# attenuverter1.net
KiCad netlist of a schematic drawn in EAGLE
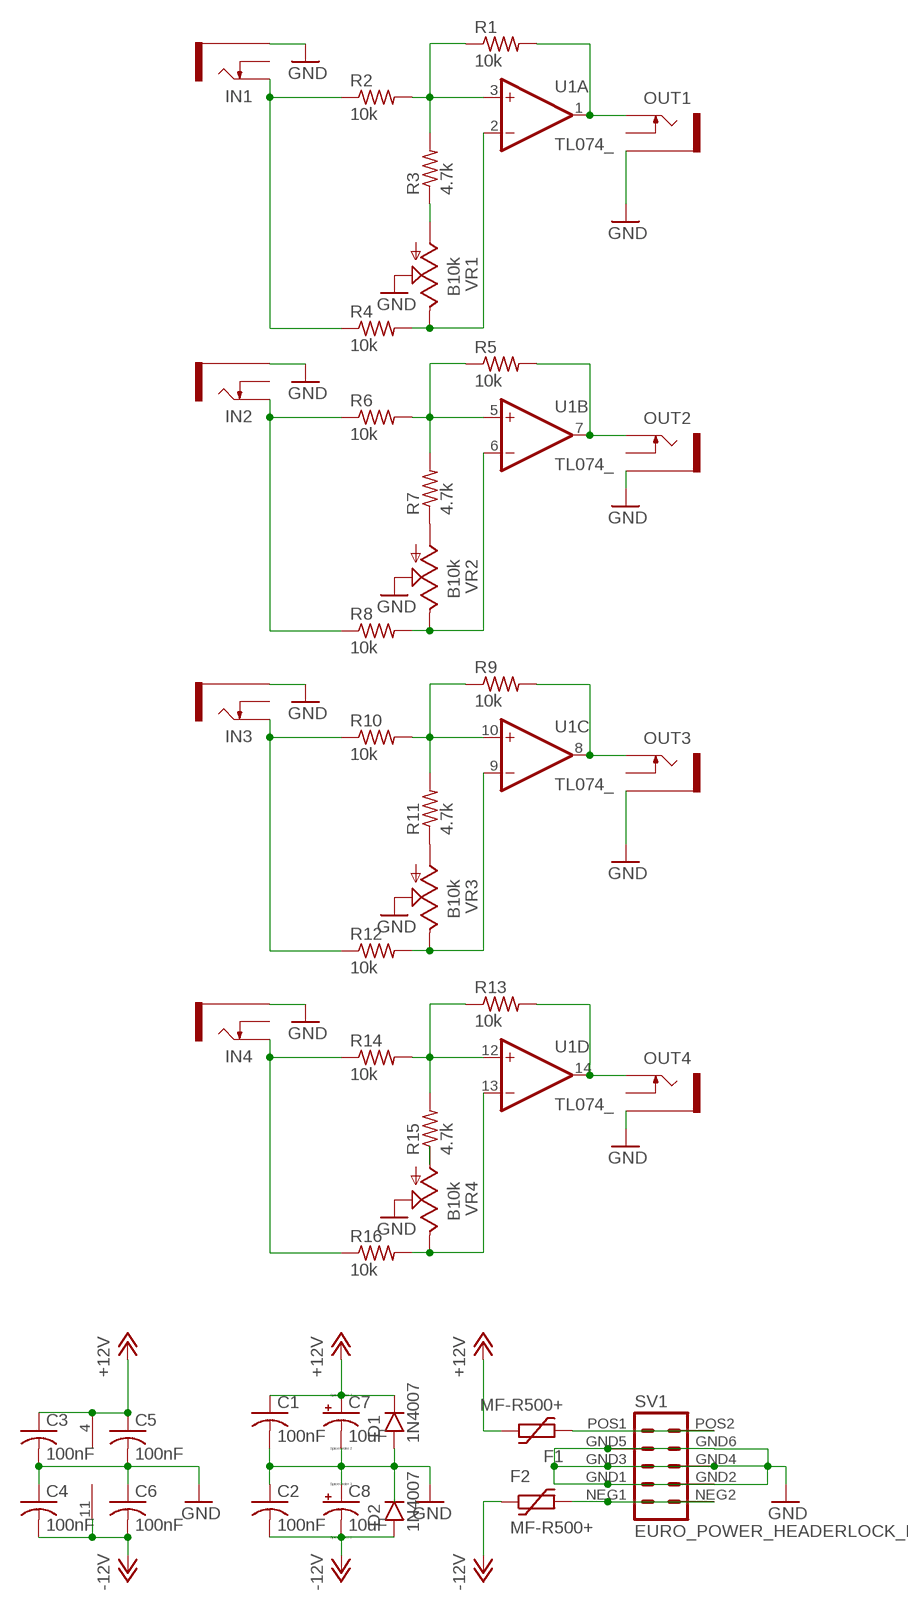
[diagram p0: schematic, sheet 1]

(export (version "E")
  (design (tool "Eeschema 10.0.6"))
  (components
    (comp (ref "C1")
      (value "100nF")
      (footprint "eagle-import:C050-055X075")
      (libsource (lib "eagle-import") (part "C-US050-055X075"))
    )
    (comp (ref "C2")
      (value "100nF")
      (footprint "eagle-import:C050-055X075")
      (libsource (lib "eagle-import") (part "C-US050-055X075"))
    )
    (comp (ref "C3")
      (value "100nF")
      (footprint "eagle-import:C050-055X075")
      (libsource (lib "eagle-import") (part "C-US050-055X075"))
    )
    (comp (ref "C4")
      (value "100nF")
      (footprint "eagle-import:C050-055X075")
      (libsource (lib "eagle-import") (part "C-US050-055X075"))
    )
    (comp (ref "C5")
      (value "100nF")
      (footprint "eagle-import:C050-055X075")
      (libsource (lib "eagle-import") (part "C-US050-055X075"))
    )
    (comp (ref "C6")
      (value "100nF")
      (footprint "eagle-import:C050-055X075")
      (libsource (lib "eagle-import") (part "C-US050-055X075"))
    )
    (comp (ref "C7")
      (value "10uF")
      (footprint "eagle-import:E2,5-6")
      (libsource (lib "eagle-import") (part "CPOL-USE2.5-6"))
    )
    (comp (ref "C8")
      (value "10uF")
      (footprint "eagle-import:E2,5-6")
      (libsource (lib "eagle-import") (part "CPOL-USE2.5-6"))
    )
    (comp (ref "D1")
      (value "1N4007")
      (footprint "eagle-import:DO41-4")
      (libsource (lib "eagle-import") (part "1N400X.4"))
    )
    (comp (ref "D2")
      (value "1N4007")
      (footprint "eagle-import:DO41-4")
      (libsource (lib "eagle-import") (part "1N400X.4"))
    )
    (comp (ref "F1")
      (value "MF-R500+")
      (footprint "eagle-import:BOURNS-MF-R")
      (libsource (lib "eagle-import") (part "MF-R500+"))
    )
    (comp (ref "F2")
      (value "MF-R500+")
      (footprint "eagle-import:BOURNS-MF-R")
      (libsource (lib "eagle-import") (part "MF-R500+"))
    )
    (comp (ref "IN1")
      (value "THONKICONNNEW")
      (footprint "eagle-import:WQP-PJ301M-12_JACK")
      (libsource (lib "eagle-import") (part "THONKICONNNEW"))
    )
    (comp (ref "IN2")
      (value "THONKICONNNEW")
      (footprint "eagle-import:WQP-PJ301M-12_JACK")
      (libsource (lib "eagle-import") (part "THONKICONNNEW"))
    )
    (comp (ref "IN3")
      (value "THONKICONNNEW")
      (footprint "eagle-import:WQP-PJ301M-12_JACK")
      (libsource (lib "eagle-import") (part "THONKICONNNEW"))
    )
    (comp (ref "IN4")
      (value "THONKICONNNEW")
      (footprint "eagle-import:WQP-PJ301M-12_JACK")
      (libsource (lib "eagle-import") (part "THONKICONNNEW"))
    )
    (comp (ref "OUT1")
      (value "THONKICONNNEW")
      (footprint "eagle-import:WQP-PJ301M-12_JACK")
      (libsource (lib "eagle-import") (part "THONKICONNNEW"))
    )
    (comp (ref "OUT2")
      (value "THONKICONNNEW")
      (footprint "eagle-import:WQP-PJ301M-12_JACK")
      (libsource (lib "eagle-import") (part "THONKICONNNEW"))
    )
    (comp (ref "OUT3")
      (value "THONKICONNNEW")
      (footprint "eagle-import:WQP-PJ301M-12_JACK")
      (libsource (lib "eagle-import") (part "THONKICONNNEW"))
    )
    (comp (ref "OUT4")
      (value "THONKICONNNEW")
      (footprint "eagle-import:WQP-PJ301M-12_JACK")
      (libsource (lib "eagle-import") (part "THONKICONNNEW"))
    )
    (comp (ref "R1")
      (value "10k")
      (footprint "eagle-import:0207_7")
      (libsource (lib "eagle-import") (part "R-US_0207/7"))
    )
    (comp (ref "R2")
      (value "10k")
      (footprint "eagle-import:0207_7")
      (libsource (lib "eagle-import") (part "R-US_0207/7"))
    )
    (comp (ref "R3")
      (value "4.7k")
      (footprint "eagle-import:0207_7")
      (libsource (lib "eagle-import") (part "R-US_0207/7"))
    )
    (comp (ref "R4")
      (value "10k")
      (footprint "eagle-import:0207_7")
      (libsource (lib "eagle-import") (part "R-US_0207/7"))
    )
    (comp (ref "R5")
      (value "10k")
      (footprint "eagle-import:0207_7")
      (libsource (lib "eagle-import") (part "R-US_0207/7"))
    )
    (comp (ref "R6")
      (value "10k")
      (footprint "eagle-import:0207_7")
      (libsource (lib "eagle-import") (part "R-US_0207/7"))
    )
    (comp (ref "R7")
      (value "4.7k")
      (footprint "eagle-import:0207_7")
      (libsource (lib "eagle-import") (part "R-US_0207/7"))
    )
    (comp (ref "R8")
      (value "10k")
      (footprint "eagle-import:0207_7")
      (libsource (lib "eagle-import") (part "R-US_0207/7"))
    )
    (comp (ref "R9")
      (value "10k")
      (footprint "eagle-import:0207_7")
      (libsource (lib "eagle-import") (part "R-US_0207/7"))
    )
    (comp (ref "R10")
      (value "10k")
      (footprint "eagle-import:0207_7")
      (libsource (lib "eagle-import") (part "R-US_0207/7"))
    )
    (comp (ref "R11")
      (value "4.7k")
      (footprint "eagle-import:0207_7")
      (libsource (lib "eagle-import") (part "R-US_0207/7"))
    )
    (comp (ref "R12")
      (value "10k")
      (footprint "eagle-import:0207_7")
      (libsource (lib "eagle-import") (part "R-US_0207/7"))
    )
    (comp (ref "R13")
      (value "10k")
      (footprint "eagle-import:0207_7")
      (libsource (lib "eagle-import") (part "R-US_0207/7"))
    )
    (comp (ref "R14")
      (value "10k")
      (footprint "eagle-import:0207_7")
      (libsource (lib "eagle-import") (part "R-US_0207/7"))
    )
    (comp (ref "R15")
      (value "4.7k")
      (footprint "eagle-import:0207_7")
      (libsource (lib "eagle-import") (part "R-US_0207/7"))
    )
    (comp (ref "R16")
      (value "10k")
      (footprint "eagle-import:0207_7")
      (libsource (lib "eagle-import") (part "R-US_0207/7"))
    )
    (comp (ref "SV1")
      (value "EURO_POWER_HEADERLOCK_PADS")
      (footprint "eagle-import:EURO_PWR_HEADER_LOCK")
      (libsource (lib "eagle-import") (part "EURO_POWER_HEADERLOCK_PADS"))
    )
    (comp (ref "U1")
      (value "TL074_")
      (footprint "eagle-import:DIL14")
      (libsource (lib "eagle-import") (part "TL074_"))
    )
    (comp (ref "VR1")
      (value "B10k")
      (footprint "eagle-import:9MM_SNAP-IN_POT")
      (libsource (lib "eagle-import") (part "9MM_SNAP-IN_POT_"))
    )
    (comp (ref "VR2")
      (value "B10k")
      (footprint "eagle-import:9MM_SNAP-IN_POT")
      (libsource (lib "eagle-import") (part "9MM_SNAP-IN_POT_"))
    )
    (comp (ref "VR3")
      (value "B10k")
      (footprint "eagle-import:9MM_SNAP-IN_POT")
      (libsource (lib "eagle-import") (part "9MM_SNAP-IN_POT_"))
    )
    (comp (ref "VR4")
      (value "B10k")
      (footprint "eagle-import:9MM_SNAP-IN_POT")
      (libsource (lib "eagle-import") (part "9MM_SNAP-IN_POT_"))
    )
  )
  (nets
    (net (code "1") (name "+12V") (class "Default")
      (node (ref "C1") (pin "1") (pinfunction "1_1") (pintype "passive"))
      (node (ref "C3") (pin "1") (pinfunction "1_1") (pintype "passive"))
      (node (ref "C5") (pin "1") (pinfunction "1_1") (pintype "passive"))
      (node (ref "C7") (pin "+") (pinfunction "+_+") (pintype "passive"))
      (node (ref "D1") (pin "C") (pinfunction "C_C") (pintype "passive"))
      (node (ref "F1") (pin "P$2") (pinfunction "2_P$2") (pintype "passive"))
      (node (ref "U1") (pin "4") (pinfunction "V+_4") (pintype "power_in"))
    )
    (net (code "2") (name "-12V") (class "Default")
      (node (ref "C2") (pin "2") (pinfunction "2_2") (pintype "passive"))
      (node (ref "C4") (pin "2") (pinfunction "2_2") (pintype "passive"))
      (node (ref "C6") (pin "2") (pinfunction "2_2") (pintype "passive"))
      (node (ref "C8") (pin "-") (pinfunction "-_-") (pintype "passive"))
      (node (ref "D2") (pin "A") (pinfunction "A_A") (pintype "passive"))
      (node (ref "F2") (pin "P$1") (pinfunction "1_P$1") (pintype "passive"))
      (node (ref "U1") (pin "11") (pinfunction "V-_11") (pintype "power_in"))
    )
    (net (code "3") (name "GND") (class "Default")
      (node (ref "C1") (pin "2") (pinfunction "2_2") (pintype "passive"))
      (node (ref "C2") (pin "1") (pinfunction "1_1") (pintype "passive"))
      (node (ref "C3") (pin "2") (pinfunction "2_2") (pintype "passive"))
      (node (ref "C4") (pin "1") (pinfunction "1_1") (pintype "passive"))
      (node (ref "C5") (pin "2") (pinfunction "2_2") (pintype "passive"))
      (node (ref "C6") (pin "1") (pinfunction "1_1") (pintype "passive"))
      (node (ref "C7") (pin "-") (pinfunction "-_-") (pintype "passive"))
      (node (ref "C8") (pin "+") (pinfunction "+_+") (pintype "passive"))
      (node (ref "D1") (pin "A") (pinfunction "A_A") (pintype "passive"))
      (node (ref "IN1") (pin "P$3_SLEEVE") (pinfunction "SLEEVE_P$3_SLEEVE") (pintype "passive"))
      (node (ref "IN2") (pin "P$3_SLEEVE") (pinfunction "SLEEVE_P$3_SLEEVE") (pintype "passive"))
      (node (ref "IN3") (pin "P$3_SLEEVE") (pinfunction "SLEEVE_P$3_SLEEVE") (pintype "passive"))
      (node (ref "IN4") (pin "P$3_SLEEVE") (pinfunction "SLEEVE_P$3_SLEEVE") (pintype "passive"))
      (node (ref "OUT1") (pin "P$3_SLEEVE") (pinfunction "SLEEVE_P$3_SLEEVE") (pintype "passive"))
      (node (ref "OUT2") (pin "P$3_SLEEVE") (pinfunction "SLEEVE_P$3_SLEEVE") (pintype "passive"))
      (node (ref "OUT3") (pin "P$3_SLEEVE") (pinfunction "SLEEVE_P$3_SLEEVE") (pintype "passive"))
      (node (ref "OUT4") (pin "P$3_SLEEVE") (pinfunction "SLEEVE_P$3_SLEEVE") (pintype "passive"))
      (node (ref "SV1") (pin "GND1") (pinfunction "4_GND1") (pintype "passive"))
      (node (ref "SV1") (pin "GND2") (pinfunction "3_GND2") (pintype "passive"))
      (node (ref "SV1") (pin "GND3") (pinfunction "6_GND3") (pintype "passive"))
      (node (ref "SV1") (pin "GND4") (pinfunction "5_GND4") (pintype "passive"))
      (node (ref "SV1") (pin "GND5") (pinfunction "8_GND5") (pintype "passive"))
      (node (ref "SV1") (pin "GND6") (pinfunction "7_GND6") (pintype "passive"))
      (node (ref "VR1") (pin "2") (pinfunction "S_2") (pintype "passive"))
      (node (ref "VR2") (pin "2") (pinfunction "S_2") (pintype "passive"))
      (node (ref "VR3") (pin "2") (pinfunction "S_2") (pintype "passive"))
      (node (ref "VR4") (pin "2") (pinfunction "S_2") (pintype "passive"))
    )
    (net (code "4") (name "Net-(F1-1)") (class "Default")
      (node (ref "F1") (pin "P$1") (pinfunction "1_P$1") (pintype "passive"))
      (node (ref "SV1") (pin "POS1") (pinfunction "10_POS1") (pintype "passive"))
      (node (ref "SV1") (pin "POS2") (pinfunction "9_POS2") (pintype "passive"))
    )
    (net (code "5") (name "Net-(F2-2)") (class "Default")
      (node (ref "F2") (pin "P$2") (pinfunction "2_P$2") (pintype "passive"))
      (node (ref "SV1") (pin "NEG1") (pinfunction "2_NEG1") (pintype "passive"))
      (node (ref "SV1") (pin "NEG2") (pinfunction "1_NEG2") (pintype "passive"))
    )
    (net (code "6") (name "Net-(IN1-TIP)") (class "Default")
      (node (ref "IN1") (pin "P$1_TIP") (pinfunction "TIP_P$1_TIP") (pintype "passive"))
      (node (ref "R2") (pin "1") (pinfunction "1_1") (pintype "passive"))
      (node (ref "R4") (pin "1") (pinfunction "1_1") (pintype "passive"))
    )
    (net (code "7") (name "Net-(IN2-TIP)") (class "Default")
      (node (ref "IN2") (pin "P$1_TIP") (pinfunction "TIP_P$1_TIP") (pintype "passive"))
      (node (ref "R6") (pin "1") (pinfunction "1_1") (pintype "passive"))
      (node (ref "R8") (pin "1") (pinfunction "1_1") (pintype "passive"))
    )
    (net (code "8") (name "Net-(IN3-TIP)") (class "Default")
      (node (ref "IN3") (pin "P$1_TIP") (pinfunction "TIP_P$1_TIP") (pintype "passive"))
      (node (ref "R10") (pin "1") (pinfunction "1_1") (pintype "passive"))
      (node (ref "R12") (pin "1") (pinfunction "1_1") (pintype "passive"))
    )
    (net (code "9") (name "Net-(IN4-TIP)") (class "Default")
      (node (ref "IN4") (pin "P$1_TIP") (pinfunction "TIP_P$1_TIP") (pintype "passive"))
      (node (ref "R14") (pin "1") (pinfunction "1_1") (pintype "passive"))
      (node (ref "R16") (pin "1") (pinfunction "1_1") (pintype "passive"))
    )
    (net (code "10") (name "Net-(OUT1-TIP)") (class "Default")
      (node (ref "OUT1") (pin "P$1_TIP") (pinfunction "TIP_P$1_TIP") (pintype "passive"))
      (node (ref "R1") (pin "2") (pinfunction "2_2") (pintype "passive"))
      (node (ref "U1") (pin "1") (pinfunction "OUT_1") (pintype "output"))
    )
    (net (code "11") (name "Net-(OUT2-TIP)") (class "Default")
      (node (ref "OUT2") (pin "P$1_TIP") (pinfunction "TIP_P$1_TIP") (pintype "passive"))
      (node (ref "R5") (pin "2") (pinfunction "2_2") (pintype "passive"))
      (node (ref "U1") (pin "7") (pinfunction "OUT_7") (pintype "output"))
    )
    (net (code "12") (name "Net-(OUT3-TIP)") (class "Default")
      (node (ref "OUT3") (pin "P$1_TIP") (pinfunction "TIP_P$1_TIP") (pintype "passive"))
      (node (ref "R9") (pin "2") (pinfunction "2_2") (pintype "passive"))
      (node (ref "U1") (pin "8") (pinfunction "OUT_8") (pintype "output"))
    )
    (net (code "13") (name "Net-(OUT4-TIP)") (class "Default")
      (node (ref "OUT4") (pin "P$1_TIP") (pinfunction "TIP_P$1_TIP") (pintype "passive"))
      (node (ref "R13") (pin "2") (pinfunction "2_2") (pintype "passive"))
      (node (ref "U1") (pin "14") (pinfunction "OUT_14") (pintype "output"))
    )
    (net (code "14") (name "Net-(U1A-+IN)") (class "Default")
      (node (ref "R1") (pin "1") (pinfunction "1_1") (pintype "passive"))
      (node (ref "R2") (pin "2") (pinfunction "2_2") (pintype "passive"))
      (node (ref "R3") (pin "2") (pinfunction "2_2") (pintype "passive"))
      (node (ref "U1") (pin "3") (pinfunction "+IN_3") (pintype "input"))
    )
    (net (code "15") (name "Net-(U1A--IN)") (class "Default")
      (node (ref "R4") (pin "2") (pinfunction "2_2") (pintype "passive"))
      (node (ref "U1") (pin "2") (pinfunction "-IN_2") (pintype "input"))
      (node (ref "VR1") (pin "3") (pinfunction "E_3") (pintype "passive"))
    )
    (net (code "16") (name "Net-(U1B-+IN)") (class "Default")
      (node (ref "R5") (pin "1") (pinfunction "1_1") (pintype "passive"))
      (node (ref "R6") (pin "2") (pinfunction "2_2") (pintype "passive"))
      (node (ref "R7") (pin "2") (pinfunction "2_2") (pintype "passive"))
      (node (ref "U1") (pin "5") (pinfunction "+IN_5") (pintype "input"))
    )
    (net (code "17") (name "Net-(U1B--IN)") (class "Default")
      (node (ref "R8") (pin "2") (pinfunction "2_2") (pintype "passive"))
      (node (ref "U1") (pin "6") (pinfunction "-IN_6") (pintype "input"))
      (node (ref "VR2") (pin "3") (pinfunction "E_3") (pintype "passive"))
    )
    (net (code "18") (name "Net-(U1C-+IN)") (class "Default")
      (node (ref "R10") (pin "2") (pinfunction "2_2") (pintype "passive"))
      (node (ref "R11") (pin "2") (pinfunction "2_2") (pintype "passive"))
      (node (ref "R9") (pin "1") (pinfunction "1_1") (pintype "passive"))
      (node (ref "U1") (pin "10") (pinfunction "+IN_10") (pintype "input"))
    )
    (net (code "19") (name "Net-(U1C--IN)") (class "Default")
      (node (ref "R12") (pin "2") (pinfunction "2_2") (pintype "passive"))
      (node (ref "U1") (pin "9") (pinfunction "-IN_9") (pintype "input"))
      (node (ref "VR3") (pin "3") (pinfunction "E_3") (pintype "passive"))
    )
    (net (code "20") (name "Net-(U1D-+IN)") (class "Default")
      (node (ref "R13") (pin "1") (pinfunction "1_1") (pintype "passive"))
      (node (ref "R14") (pin "2") (pinfunction "2_2") (pintype "passive"))
      (node (ref "R15") (pin "2") (pinfunction "2_2") (pintype "passive"))
      (node (ref "U1") (pin "12") (pinfunction "+IN_12") (pintype "input"))
    )
    (net (code "21") (name "Net-(U1D--IN)") (class "Default")
      (node (ref "R16") (pin "2") (pinfunction "2_2") (pintype "passive"))
      (node (ref "U1") (pin "13") (pinfunction "-IN_13") (pintype "input"))
      (node (ref "VR4") (pin "3") (pinfunction "E_3") (pintype "passive"))
    )
    (net (code "22") (name "Net-(VR1-A)") (class "Default")
      (node (ref "R3") (pin "1") (pinfunction "1_1") (pintype "passive"))
      (node (ref "VR1") (pin "1") (pinfunction "A_1") (pintype "passive"))
    )
    (net (code "23") (name "Net-(VR2-A)") (class "Default")
      (node (ref "R7") (pin "1") (pinfunction "1_1") (pintype "passive"))
      (node (ref "VR2") (pin "1") (pinfunction "A_1") (pintype "passive"))
    )
    (net (code "24") (name "Net-(VR3-A)") (class "Default")
      (node (ref "R11") (pin "1") (pinfunction "1_1") (pintype "passive"))
      (node (ref "VR3") (pin "1") (pinfunction "A_1") (pintype "passive"))
    )
    (net (code "25") (name "Net-(VR4-A)") (class "Default")
      (node (ref "R15") (pin "1") (pinfunction "1_1") (pintype "passive"))
      (node (ref "VR4") (pin "1") (pinfunction "A_1") (pintype "passive"))
    )
    (net (code "26") (name "unconnected-(D2-PadC)") (class "Default")
      (node (ref "D2") (pin "C") (pinfunction "C_C") (pintype "passive"))
    )
    (net (code "27") (name "unconnected-(IN1-SWITCH-PadP$2_SWITCH)") (class "Default")
      (node (ref "IN1") (pin "P$2_SWITCH") (pinfunction "SWITCH_P$2_SWITCH") (pintype "passive"))
    )
    (net (code "28") (name "unconnected-(IN2-SWITCH-PadP$2_SWITCH)") (class "Default")
      (node (ref "IN2") (pin "P$2_SWITCH") (pinfunction "SWITCH_P$2_SWITCH") (pintype "passive"))
    )
    (net (code "29") (name "unconnected-(IN3-SWITCH-PadP$2_SWITCH)") (class "Default")
      (node (ref "IN3") (pin "P$2_SWITCH") (pinfunction "SWITCH_P$2_SWITCH") (pintype "passive"))
    )
    (net (code "30") (name "unconnected-(IN4-SWITCH-PadP$2_SWITCH)") (class "Default")
      (node (ref "IN4") (pin "P$2_SWITCH") (pinfunction "SWITCH_P$2_SWITCH") (pintype "passive"))
    )
    (net (code "31") (name "unconnected-(OUT1-SWITCH-PadP$2_SWITCH)") (class "Default")
      (node (ref "OUT1") (pin "P$2_SWITCH") (pinfunction "SWITCH_P$2_SWITCH") (pintype "passive"))
    )
    (net (code "32") (name "unconnected-(OUT2-SWITCH-PadP$2_SWITCH)") (class "Default")
      (node (ref "OUT2") (pin "P$2_SWITCH") (pinfunction "SWITCH_P$2_SWITCH") (pintype "passive"))
    )
    (net (code "33") (name "unconnected-(OUT3-SWITCH-PadP$2_SWITCH)") (class "Default")
      (node (ref "OUT3") (pin "P$2_SWITCH") (pinfunction "SWITCH_P$2_SWITCH") (pintype "passive"))
    )
    (net (code "34") (name "unconnected-(OUT4-SWITCH-PadP$2_SWITCH)") (class "Default")
      (node (ref "OUT4") (pin "P$2_SWITCH") (pinfunction "SWITCH_P$2_SWITCH") (pintype "passive"))
    )
  )
)
